# Beetech_GSM_MKR1400.net
KiCad netlist of a schematic drawn in Altium Designer
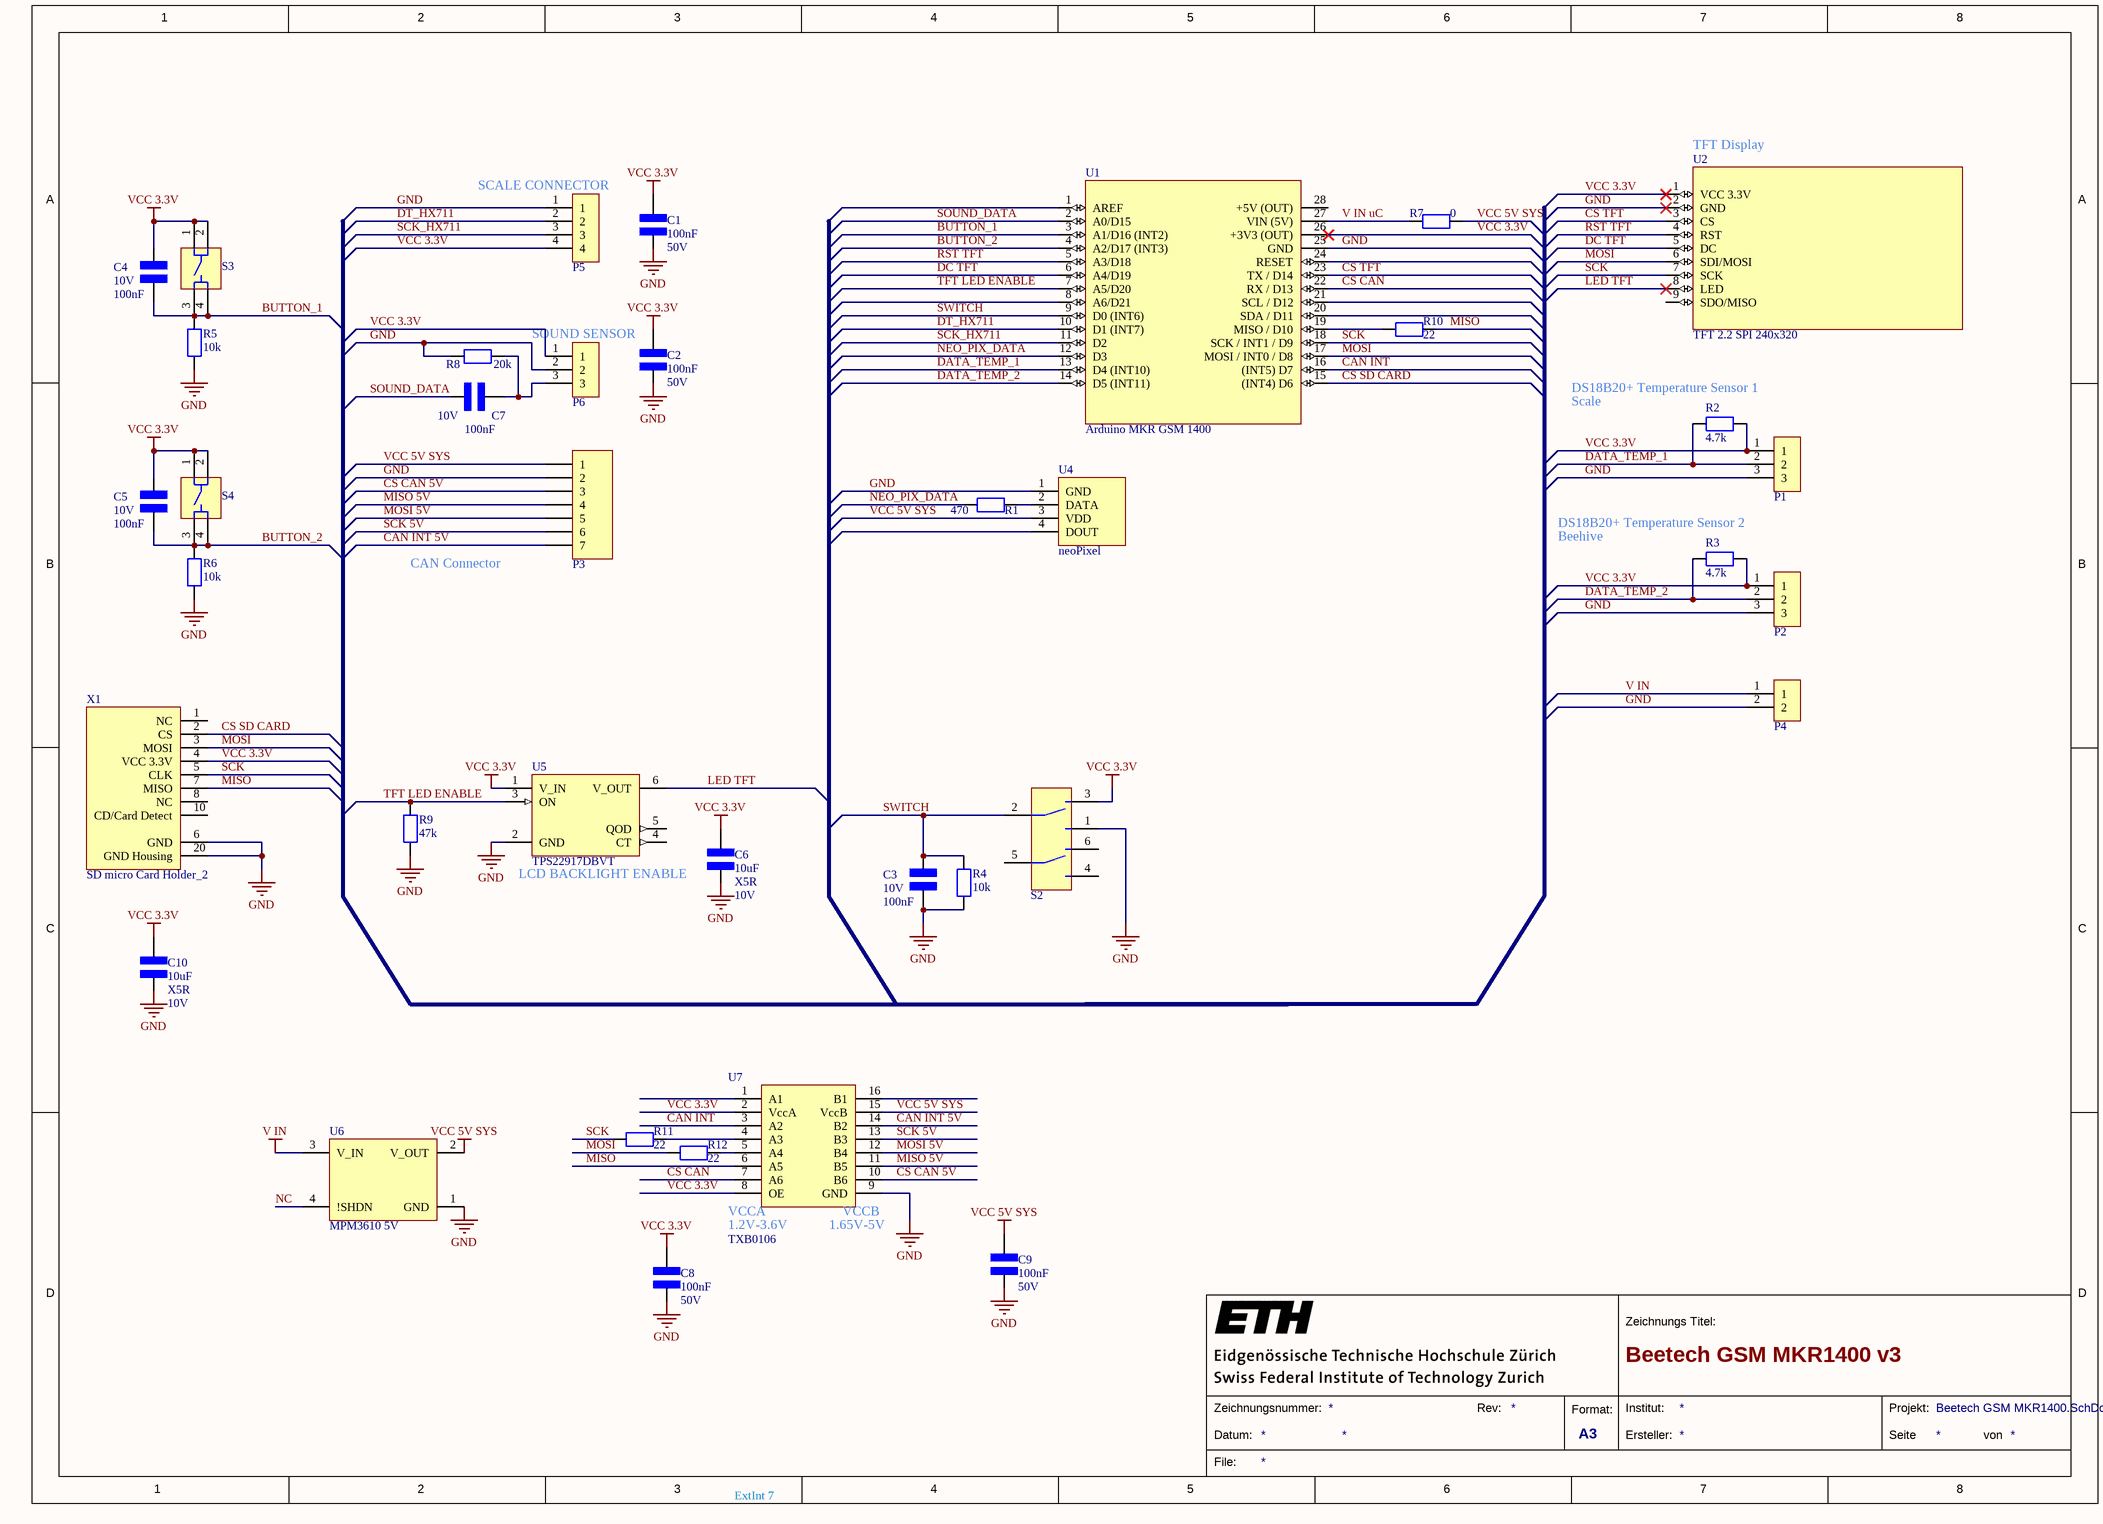
[diagram p0: Beetech GSM MKR1400.SchDoc]

(export (version "E")
  (design (tool "Eeschema 10.0.6"))
  (components
    (comp (ref "C1")
      (value "100nF")
      (footprint "CAP 0603")
      (description "C CERAMIC SMD")
      (fields (field (name "UMAX") "50V") (field (name "Comment") "100nF 0603_1"))
      (libsource (lib "Library CAP") (part "100nF 0603_1"))
    )
    (comp (ref "C2")
      (value "100nF")
      (footprint "CAP 0603")
      (description "C CERAMIC SMD")
      (fields (field (name "UMAX") "50V") (field (name "Comment") "100nF 0603_1"))
      (libsource (lib "Library CAP") (part "100nF 0603_1"))
    )
    (comp (ref "C3")
      (value "100nF")
      (footprint "CAP 0603")
      (description "C CERAMIC SMD")
      (fields (field (name "UMAX") "10V") (field (name "Comment") "100nF 0603"))
      (libsource (lib "Library CAP") (part "100nF 0603"))
    )
    (comp (ref "C4")
      (value "100nF")
      (footprint "CAP 0603")
      (description "C CERAMIC SMD")
      (fields (field (name "UMAX") "10V") (field (name "Comment") "100nF 0603"))
      (libsource (lib "Library CAP") (part "100nF 0603"))
    )
    (comp (ref "C5")
      (value "100nF")
      (footprint "CAP 0603")
      (description "C CERAMIC SMD")
      (fields (field (name "UMAX") "10V") (field (name "Comment") "100nF 0603"))
      (libsource (lib "Library CAP") (part "100nF 0603"))
    )
    (comp (ref "C6")
      (value "10uF")
      (footprint "CAP 0603")
      (description "C CERAMIC SMD")
      (fields
        (field (name "DIELEKTRIKUM") "X5R")
        (field (name "UMAX") "10V")
        (field (name "Comment") "10uF 0603")
      )
      (libsource (lib "Library CAP") (part "10uF 0603"))
    )
    (comp (ref "C7")
      (value "100nF")
      (footprint "CAP 0603")
      (description "C CERAMIC SMD")
      (fields (field (name "UMAX") "10V") (field (name "Comment") "100nF 0603"))
      (libsource (lib "") (part "100nF 0603_1"))
    )
    (comp (ref "C8")
      (value "100nF")
      (footprint "CAP 0603")
      (description "C CERAMIC SMD")
      (fields (field (name "UMAX") "50V") (field (name "Comment") "100nF 0603_1"))
      (libsource (lib "Library CAP") (part "100nF 0603_1"))
    )
    (comp (ref "C9")
      (value "100nF")
      (footprint "CAP 0603")
      (description "C CERAMIC SMD")
      (fields (field (name "UMAX") "50V") (field (name "Comment") "100nF 0603_1"))
      (libsource (lib "Library CAP") (part "100nF 0603_1"))
    )
    (comp (ref "C10")
      (value "10uF")
      (footprint "CAP 0603")
      (description "C CERAMIC SMD")
      (fields
        (field (name "DIELEKTRIKUM") "X5R")
        (field (name "UMAX") "10V")
        (field (name "Comment") "10uF 0603")
      )
      (libsource (lib "Library CAP") (part "10uF 0603"))
    )
    (comp (ref "P1")
      (value "3-Pin Right Angle Housing")
      (footprint "3PIN - RND 205-EK254-2.54-03P")
      (description "3-Pin")
      (libsource (lib "Library Scematic") (part "3-Pin Screw Terminal"))
    )
    (comp (ref "P2")
      (value "3-Pin Right Angle Housing")
      (footprint "3PIN - RND 205-EK254-2.54-03P")
      (description "3-Pin")
      (libsource (lib "Library Scematic") (part "3-Pin Screw Terminal"))
    )
    (comp (ref "P3")
      (value "8-Pin")
      (footprint "7PIN")
      (fields (field (name "PUBLISHER") "Altium Limited"))
      (libsource (lib "Library Scematic") (part "7-Pin"))
    )
    (comp (ref "P4")
      (value "2-Pin Right Angle Housing")
      (footprint "2PIN - RND 205-EK254-2.54-02P")
      (description "2-Pin")
      (libsource (lib "Library Scematic") (part "2-Pin Screw Terminal"))
    )
    (comp (ref "P5")
      (value "4-Pin Right Angle Housing")
      (footprint "4PIN - RND 205-EK254-2.54-04P")
      (description "4-Pin")
      (libsource (lib "Library Scematic") (part "4-Pin Screw Terminal"))
    )
    (comp (ref "P6")
      (value "3-Pin Right Angle Housing")
      (footprint "3PIN - RND 205-EK254-2.54-03P")
      (description "3-Pin")
      (libsource (lib "Library Scematic") (part "3-Pin Screw Terminal"))
    )
    (comp (ref "R1")
      (value "470")
      (footprint "RES 0603 FOOTPRINT")
      (description "R SMD")
      (fields (field (name "Comment") "470 Ohm 0603"))
      (libsource (lib "Library RES") (part "470 Ohm 0603"))
    )
    (comp (ref "R2")
      (value "4.7k")
      (footprint "RES 0603 FOOTPRINT")
      (description "R SMD")
      (fields (field (name "Comment") "4.7k Ohm 0603"))
      (libsource (lib "Library RES") (part "4.7k Ohm 0603"))
    )
    (comp (ref "R3")
      (value "4.7k")
      (footprint "RES 0603 FOOTPRINT")
      (description "R SMD")
      (fields (field (name "Comment") "4.7k Ohm 0603"))
      (libsource (lib "Library RES") (part "4.7k Ohm 0603"))
    )
    (comp (ref "R4")
      (value "10k")
      (footprint "RES 0603 FOOTPRINT")
      (description "R SMD")
      (fields (field (name "Comment") "10k Ohm 0603"))
      (libsource (lib "Library RES") (part "10k Ohm 0603"))
    )
    (comp (ref "R5")
      (value "10k")
      (footprint "RES 0603 FOOTPRINT")
      (description "R SMD")
      (fields (field (name "Comment") "10k Ohm 0603"))
      (libsource (lib "Library RES") (part "10k Ohm 0603"))
    )
    (comp (ref "R6")
      (value "10k")
      (footprint "RES 0603 FOOTPRINT")
      (description "R SMD")
      (fields (field (name "Comment") "10k Ohm 0603"))
      (libsource (lib "Library RES") (part "10k Ohm 0603"))
    )
    (comp (ref "R7")
      (value "0")
      (footprint "RES 0603 FOOTPRINT")
      (description "R SMD")
      (fields (field (name "Comment") "0 Ohm 0603"))
      (libsource (lib "Library RES") (part "0 Ohm 0603"))
    )
    (comp (ref "R8")
      (value "20k")
      (footprint "RES 0603 FOOTPRINT")
      (description "R SMD")
      (fields (field (name "Comment") "20k Ohm 0603"))
      (libsource (lib "Library RES") (part "20k Ohm 0603"))
    )
    (comp (ref "R9")
      (value "47k")
      (footprint "RES 0603 FOOTPRINT")
      (description "R SMD")
      (fields (field (name "Comment") "47k Ohm 0603"))
      (libsource (lib "Library RES") (part "47k Ohm 0603"))
    )
    (comp (ref "R10")
      (value "22")
      (footprint "RES 0603 FOOTPRINT")
      (description "R SMD")
      (fields (field (name "Comment") "22 Ohm 0603"))
      (libsource (lib "Library RES") (part "22 Ohm 0603"))
    )
    (comp (ref "R11")
      (value "22")
      (footprint "RES 0603 FOOTPRINT")
      (description "R SMD")
      (fields (field (name "Comment") "22 Ohm 0603"))
      (libsource (lib "Library RES") (part "22 Ohm 0603"))
    )
    (comp (ref "R12")
      (value "22")
      (footprint "RES 0603 FOOTPRINT")
      (description "R SMD")
      (fields (field (name "Comment") "22 Ohm 0603"))
      (libsource (lib "Library RES") (part "22 Ohm 0603"))
    )
    (comp (ref "S2")
      (value "Schiebeschalter EG2207")
      (footprint "Schiebeschalter on-on 2 P, EG2207")
      (description "Schiebeschalter on-on PCM12SMTR")
      (libsource (lib "Library Scematic") (part "Schiebeschalter EG2207"))
    )
    (comp (ref "S3")
      (value "Taster Print_SMD_3")
      (footprint "Taster Print - SMD - PTS647SM70SMTR2LFS")
      (description "Taster")
      (libsource (lib "Library Scematic") (part "Taster Print_SMD_6"))
    )
    (comp (ref "S4")
      (value "Taster Print_SMD_3")
      (footprint "Taster Print - SMD - PTS647SM70SMTR2LFS")
      (description "Taster")
      (libsource (lib "Library Scematic") (part "Taster Print_SMD_6"))
    )
    (comp (ref "U1")
      (value "Arduino MKR GSM 1400")
      (footprint "Arduino GSM MKR 1400 v2")
      (description "https://store.arduino.cc/arduino-mkr-gsm-1400-1415")
      (libsource (lib "Library Scematic") (part "Arduino MKR GSM 1400"))
    )
    (comp (ref "U2")
      (value "TFT 2.2 SPI 240x320")
      (footprint "TFT 2.2 SPI 240x320")
      (libsource (lib "Library Scematic") (part "TFT 2.2 SPI 240x320"))
    )
    (comp (ref "U4")
      (value "neoPixel")
      (footprint "neoPixel 5050 adafruit 1655")
      (description "neoPixel 5050 adafruit 1655")
      (libsource (lib "Library Scematic") (part "neoPixel 5050 adafruit 1655"))
    )
    (comp (ref "U5")
      (value "TPS22917DBVT")
      (footprint "SOT23 - 6")
      (description "High Side Switch")
      (libsource (lib "Library Scematic") (part "TPS22917DBVT"))
    )
    (comp (ref "U6")
      (value "MPM3610 5V")
      (footprint "MPM3610 Buck Converter")
      (description "MPM3610 5V Buck Converter Breakout - 21V In 5V Out at 1.2A")
      (libsource (lib "Library PWR") (part "MPM3610 5V Buck Converter Breakout"))
    )
    (comp (ref "U7")
      (value "TXB0106")
      (footprint "TSSOP-16L")
      (description "Level Converter TXB0106")
      (libsource (lib "Library Scematic") (part "TXB0106 Level Converter"))
    )
    (comp (ref "X1")
      (value "SD micro Card Holder_2")
      (footprint "SD Card Holder - micro - 2 - sd Card inserted")
      (description "SD micro Card  Holder")
      (libsource (lib "Library Scematic") (part "SD micro Card Holder_2"))
    )
  )
  (nets
    (net (code "1") (name "/BUTTON_1") (class "Default")
      (node (ref "C4") (pin "2") (pinfunction "2_2") (pintype "passive"))
      (node (ref "R5") (pin "2") (pinfunction "2_2") (pintype "passive"))
      (node (ref "S3") (pin "3") (pinfunction "3_3") (pintype "passive"))
      (node (ref "S3") (pin "4") (pinfunction "4_4") (pintype "passive"))
      (node (ref "U1") (pin "3") (pinfunction "A1/D16_(INT2)_3") (pintype "bidirectional"))
    )
    (net (code "2") (name "/BUTTON_2") (class "Default")
      (node (ref "C5") (pin "2") (pinfunction "2_2") (pintype "passive"))
      (node (ref "R6") (pin "2") (pinfunction "2_2") (pintype "passive"))
      (node (ref "S4") (pin "3") (pinfunction "3_3") (pintype "passive"))
      (node (ref "S4") (pin "4") (pinfunction "4_4") (pintype "passive"))
      (node (ref "U1") (pin "4") (pinfunction "A2/D17_(INT3)_4") (pintype "bidirectional"))
    )
    (net (code "3") (name "/CAN INT") (class "Default")
      (node (ref "U1") (pin "16") (pinfunction "(INT5)_D7_16") (pintype "bidirectional"))
      (node (ref "U7") (pin "3") (pinfunction "A2_3") (pintype "passive"))
    )
    (net (code "4") (name "/CAN INT 5V") (class "Default")
      (node (ref "P3") (pin "7") (pinfunction "7_7") (pintype "passive"))
      (node (ref "U7") (pin "14") (pinfunction "B2_14") (pintype "passive"))
    )
    (net (code "5") (name "/CS CAN") (class "Default")
      (node (ref "U1") (pin "22") (pinfunction "RX_/_D13_22") (pintype "bidirectional"))
      (node (ref "U7") (pin "7") (pinfunction "A6_7") (pintype "passive"))
    )
    (net (code "6") (name "/CS CAN 5V") (class "Default")
      (node (ref "P3") (pin "3") (pinfunction "3_3") (pintype "passive"))
      (node (ref "U7") (pin "10") (pinfunction "B6_10") (pintype "passive"))
    )
    (net (code "7") (name "/CS SD CARD") (class "Default")
      (node (ref "U1") (pin "15") (pinfunction "(INT4)_D6_15") (pintype "bidirectional"))
      (node (ref "X1") (pin "2") (pinfunction "CS_2") (pintype "passive"))
    )
    (net (code "8") (name "/CS TFT") (class "Default")
      (node (ref "U1") (pin "23") (pinfunction "TX_/_D14_23") (pintype "bidirectional"))
      (node (ref "U2") (pin "3") (pinfunction "CS_3") (pintype "bidirectional"))
    )
    (net (code "9") (name "/DATA_TEMP_1") (class "Default")
      (node (ref "P1") (pin "2") (pinfunction "2_2") (pintype "passive"))
      (node (ref "R2") (pin "2") (pinfunction "2_2") (pintype "passive"))
      (node (ref "U1") (pin "13") (pinfunction "D4_(INT10)_13") (pintype "bidirectional"))
    )
    (net (code "10") (name "/DATA_TEMP_2") (class "Default")
      (node (ref "P2") (pin "2") (pinfunction "2_2") (pintype "passive"))
      (node (ref "R3") (pin "2") (pinfunction "2_2") (pintype "passive"))
      (node (ref "U1") (pin "14") (pinfunction "D5_(INT11)_14") (pintype "bidirectional"))
    )
    (net (code "11") (name "/DC TFT") (class "Default")
      (node (ref "U1") (pin "6") (pinfunction "A4/D19_6") (pintype "bidirectional"))
      (node (ref "U2") (pin "5") (pinfunction "DC_5") (pintype "bidirectional"))
    )
    (net (code "12") (name "/DT_HX711") (class "Default")
      (node (ref "P5") (pin "2") (pinfunction "2_2") (pintype "passive"))
      (node (ref "U1") (pin "10") (pinfunction "D1_(INT7)_10") (pintype "bidirectional"))
    )
    (net (code "13") (name "/LED TFT") (class "Default")
      (node (ref "U2") (pin "8") (pinfunction "LED_8") (pintype "bidirectional"))
      (node (ref "U5") (pin "6") (pinfunction "V_OUT_6") (pintype "power_in"))
    )
    (net (code "14") (name "/MISO") (class "Default")
      (node (ref "R10") (pin "2") (pinfunction "2_2") (pintype "passive"))
      (node (ref "U7") (pin "6") (pinfunction "A5_6") (pintype "passive"))
      (node (ref "X1") (pin "7") (pinfunction "MISO_7") (pintype "passive"))
    )
    (net (code "15") (name "/MISO 5V") (class "Default")
      (node (ref "P3") (pin "4") (pinfunction "4_4") (pintype "passive"))
      (node (ref "U7") (pin "11") (pinfunction "B5_11") (pintype "passive"))
    )
    (net (code "16") (name "/MOSI") (class "Default")
      (node (ref "R12") (pin "1") (pinfunction "1_1") (pintype "passive"))
      (node (ref "U1") (pin "17") (pinfunction "MOSI_/_INT0_/_D8_17") (pintype "bidirectional"))
      (node (ref "U2") (pin "6") (pinfunction "SDI/MOSI_6") (pintype "bidirectional"))
      (node (ref "X1") (pin "3") (pinfunction "MOSI_3") (pintype "passive"))
    )
    (net (code "17") (name "/MOSI 5V") (class "Default")
      (node (ref "P3") (pin "5") (pinfunction "5_5") (pintype "passive"))
      (node (ref "U7") (pin "12") (pinfunction "B4_12") (pintype "passive"))
    )
    (net (code "18") (name "/NC") (class "Default")
      (node (ref "U6") (pin "4") (pinfunction "!SHDN_4") (pintype "power_in"))
    )
    (net (code "19") (name "/NEO_PIX_DATA") (class "Default")
      (node (ref "R1") (pin "1") (pinfunction "1_1") (pintype "passive"))
      (node (ref "U1") (pin "12") (pinfunction "D3_12") (pintype "bidirectional"))
    )
    (net (code "20") (name "/RST TFT") (class "Default")
      (node (ref "U1") (pin "5") (pinfunction "A3/D18_5") (pintype "bidirectional"))
      (node (ref "U2") (pin "4") (pinfunction "RST_4") (pintype "bidirectional"))
    )
    (net (code "21") (name "/SCK") (class "Default")
      (node (ref "R11") (pin "1") (pinfunction "1_1") (pintype "passive"))
      (node (ref "U1") (pin "18") (pinfunction "SCK_/_INT1_/_D9_18") (pintype "bidirectional"))
      (node (ref "U2") (pin "7") (pinfunction "SCK_7") (pintype "bidirectional"))
      (node (ref "X1") (pin "5") (pinfunction "CLK_5") (pintype "passive"))
    )
    (net (code "22") (name "/SCK 5V") (class "Default")
      (node (ref "P3") (pin "6") (pinfunction "6_6") (pintype "passive"))
      (node (ref "U7") (pin "13") (pinfunction "B3_13") (pintype "passive"))
    )
    (net (code "23") (name "/SCK_HX711") (class "Default")
      (node (ref "P5") (pin "3") (pinfunction "3_3") (pintype "passive"))
      (node (ref "U1") (pin "11") (pinfunction "D2_11") (pintype "bidirectional"))
    )
    (net (code "24") (name "/SOUND_DATA") (class "Default")
      (node (ref "C7") (pin "1") (pinfunction "1_1") (pintype "passive"))
      (node (ref "U1") (pin "2") (pinfunction "A0/D15_2") (pintype "bidirectional"))
    )
    (net (code "25") (name "/SWITCH") (class "Default")
      (node (ref "C3") (pin "1") (pinfunction "1_1") (pintype "passive"))
      (node (ref "R4") (pin "2") (pinfunction "2_2") (pintype "passive"))
      (node (ref "S2") (pin "2") (pinfunction "2_2") (pintype "passive"))
      (node (ref "U1") (pin "9") (pinfunction "D0_(INT6)_9") (pintype "bidirectional"))
    )
    (net (code "26") (name "/TFT LED ENABLE") (class "Default")
      (node (ref "R9") (pin "2") (pinfunction "2_2") (pintype "passive"))
      (node (ref "U1") (pin "7") (pinfunction "A5/D20_7") (pintype "bidirectional"))
      (node (ref "U5") (pin "3") (pinfunction "ON_3") (pintype "input"))
    )
    (net (code "27") (name "/V IN uC") (class "Default")
      (node (ref "R7") (pin "1") (pinfunction "1_1") (pintype "passive"))
      (node (ref "U1") (pin "27") (pinfunction "VIN_(5V)_27") (pintype "power_in"))
    )
    (net (code "28") (name "GND") (class "Default")
      (node (ref "C1") (pin "1") (pinfunction "1_1") (pintype "passive"))
      (node (ref "C10") (pin "1") (pinfunction "1_1") (pintype "passive"))
      (node (ref "C2") (pin "1") (pinfunction "1_1") (pintype "passive"))
      (node (ref "C3") (pin "2") (pinfunction "2_2") (pintype "passive"))
      (node (ref "C6") (pin "1") (pinfunction "1_1") (pintype "passive"))
      (node (ref "C8") (pin "1") (pinfunction "1_1") (pintype "passive"))
      (node (ref "C9") (pin "1") (pinfunction "1_1") (pintype "passive"))
      (node (ref "P1") (pin "3") (pinfunction "3_3") (pintype "passive"))
      (node (ref "P2") (pin "3") (pinfunction "3_3") (pintype "passive"))
      (node (ref "P3") (pin "2") (pinfunction "2_2") (pintype "passive"))
      (node (ref "P4") (pin "2") (pinfunction "2_2") (pintype "passive"))
      (node (ref "P5") (pin "1") (pinfunction "1_1") (pintype "passive"))
      (node (ref "P6") (pin "2") (pinfunction "2_2") (pintype "passive"))
      (node (ref "R4") (pin "1") (pinfunction "1_1") (pintype "passive"))
      (node (ref "R5") (pin "1") (pinfunction "1_1") (pintype "passive"))
      (node (ref "R6") (pin "1") (pinfunction "1_1") (pintype "passive"))
      (node (ref "R8") (pin "1") (pinfunction "1_1") (pintype "passive"))
      (node (ref "R9") (pin "1") (pinfunction "1_1") (pintype "passive"))
      (node (ref "S2") (pin "1") (pinfunction "1_1") (pintype "passive"))
      (node (ref "U1") (pin "25") (pinfunction "GND_25") (pintype "power_in"))
      (node (ref "U2") (pin "2") (pinfunction "GND_2") (pintype "bidirectional"))
      (node (ref "U4") (pin "1") (pinfunction "GND_1") (pintype "passive"))
      (node (ref "U5") (pin "2") (pinfunction "GND_2") (pintype "power_in"))
      (node (ref "U6") (pin "1") (pinfunction "GND_1") (pintype "power_in"))
      (node (ref "U7") (pin "9") (pinfunction "GND_9") (pintype "passive"))
      (node (ref "X1") (pin "20") (pinfunction "GND_Housing_20") (pintype "passive"))
      (node (ref "X1") (pin "6") (pinfunction "GND_6") (pintype "passive"))
    )
    (net (code "29") (name "Net-(C7-Pad2)") (class "Default")
      (node (ref "C7") (pin "2") (pinfunction "2_2") (pintype "passive"))
      (node (ref "P6") (pin "3") (pinfunction "3_3") (pintype "passive"))
      (node (ref "R8") (pin "2") (pinfunction "2_2") (pintype "passive"))
    )
    (net (code "30") (name "Net-(U1-MISO_{slash}_D10)") (class "Default")
      (node (ref "R10") (pin "1") (pinfunction "1_1") (pintype "passive"))
      (node (ref "U1") (pin "19") (pinfunction "MISO_/_D10_19") (pintype "bidirectional"))
    )
    (net (code "31") (name "Net-(U4-DATA)") (class "Default")
      (node (ref "R1") (pin "2") (pinfunction "2_2") (pintype "passive"))
      (node (ref "U4") (pin "2") (pinfunction "DATA_2") (pintype "passive"))
    )
    (net (code "32") (name "Net-(U7-A3)") (class "Default")
      (node (ref "R11") (pin "2") (pinfunction "2_2") (pintype "passive"))
      (node (ref "U7") (pin "4") (pinfunction "A3_4") (pintype "passive"))
    )
    (net (code "33") (name "Net-(U7-A4)") (class "Default")
      (node (ref "R12") (pin "2") (pinfunction "2_2") (pintype "passive"))
      (node (ref "U7") (pin "5") (pinfunction "A4_5") (pintype "passive"))
    )
    (net (code "34") (name "V IN") (class "Default")
      (node (ref "P4") (pin "1") (pinfunction "1_1") (pintype "passive"))
      (node (ref "U6") (pin "3") (pinfunction "V_IN_3") (pintype "power_in"))
    )
    (net (code "35") (name "VCC 3.3V") (class "Default")
      (node (ref "C1") (pin "2") (pinfunction "2_2") (pintype "passive"))
      (node (ref "C10") (pin "2") (pinfunction "2_2") (pintype "passive"))
      (node (ref "C2") (pin "2") (pinfunction "2_2") (pintype "passive"))
      (node (ref "C4") (pin "1") (pinfunction "1_1") (pintype "passive"))
      (node (ref "C5") (pin "1") (pinfunction "1_1") (pintype "passive"))
      (node (ref "C6") (pin "2") (pinfunction "2_2") (pintype "passive"))
      (node (ref "C8") (pin "2") (pinfunction "2_2") (pintype "passive"))
      (node (ref "P1") (pin "1") (pinfunction "1_1") (pintype "passive"))
      (node (ref "P2") (pin "1") (pinfunction "1_1") (pintype "passive"))
      (node (ref "P5") (pin "4") (pinfunction "4_4") (pintype "passive"))
      (node (ref "P6") (pin "1") (pinfunction "1_1") (pintype "passive"))
      (node (ref "R2") (pin "1") (pinfunction "1_1") (pintype "passive"))
      (node (ref "R3") (pin "1") (pinfunction "1_1") (pintype "passive"))
      (node (ref "S2") (pin "3") (pinfunction "3_3") (pintype "passive"))
      (node (ref "S3") (pin "1") (pinfunction "1_1") (pintype "passive"))
      (node (ref "S3") (pin "2") (pinfunction "2_2") (pintype "passive"))
      (node (ref "S4") (pin "1") (pinfunction "1_1") (pintype "passive"))
      (node (ref "S4") (pin "2") (pinfunction "2_2") (pintype "passive"))
      (node (ref "U1") (pin "26") (pinfunction "+3V3_(OUT)_26") (pintype "power_in"))
      (node (ref "U2") (pin "1") (pinfunction "VCC_3.3V_1") (pintype "bidirectional"))
      (node (ref "U5") (pin "1") (pinfunction "V_IN_1") (pintype "power_in"))
      (node (ref "U7") (pin "2") (pinfunction "VccA_2") (pintype "passive"))
      (node (ref "U7") (pin "8") (pinfunction "OE_8") (pintype "passive"))
      (node (ref "X1") (pin "4") (pinfunction "VCC_3.3V_4") (pintype "passive"))
    )
    (net (code "36") (name "VCC 5V SYS") (class "Default")
      (node (ref "C9") (pin "2") (pinfunction "2_2") (pintype "passive"))
      (node (ref "P3") (pin "1") (pinfunction "1_1") (pintype "passive"))
      (node (ref "R7") (pin "2") (pinfunction "2_2") (pintype "passive"))
      (node (ref "U4") (pin "3") (pinfunction "VDD_3") (pintype "passive"))
      (node (ref "U6") (pin "2") (pinfunction "V_OUT_2") (pintype "power_in"))
      (node (ref "U7") (pin "15") (pinfunction "VccB_15") (pintype "passive"))
    )
    (net (code "37") (name "unconnected-(S2-Pad4)") (class "Default")
      (node (ref "S2") (pin "4") (pinfunction "4_4") (pintype "passive"))
    )
    (net (code "38") (name "unconnected-(S2-Pad5)") (class "Default")
      (node (ref "S2") (pin "5") (pinfunction "5_5") (pintype "passive"))
    )
    (net (code "39") (name "unconnected-(S2-Pad6)") (class "Default")
      (node (ref "S2") (pin "6") (pinfunction "6_6") (pintype "passive"))
    )
    (net (code "40") (name "unconnected-(U1-+5V_(OUT)-Pad28)") (class "Default")
      (node (ref "U1") (pin "28") (pinfunction "+5V_(OUT)_28") (pintype "power_in"))
    )
    (net (code "41") (name "unconnected-(U1-A6{slash}D21-Pad8)") (class "Default")
      (node (ref "U1") (pin "8") (pinfunction "A6/D21_8") (pintype "bidirectional"))
    )
    (net (code "42") (name "unconnected-(U1-AREF-Pad1)") (class "Default")
      (node (ref "U1") (pin "1") (pinfunction "AREF_1") (pintype "bidirectional"))
    )
    (net (code "43") (name "unconnected-(U1-RESET-Pad24)") (class "Default")
      (node (ref "U1") (pin "24") (pinfunction "RESET_24") (pintype "bidirectional"))
    )
    (net (code "44") (name "unconnected-(U1-SCL_{slash}_D12-Pad21)") (class "Default")
      (node (ref "U1") (pin "21") (pinfunction "SCL_/_D12_21") (pintype "bidirectional"))
    )
    (net (code "45") (name "unconnected-(U1-SDA_{slash}_D11-Pad20)") (class "Default")
      (node (ref "U1") (pin "20") (pinfunction "SDA_/_D11_20") (pintype "bidirectional"))
    )
    (net (code "46") (name "unconnected-(U2-SDO{slash}MISO-Pad9)") (class "Default")
      (node (ref "U2") (pin "9") (pinfunction "SDO/MISO_9") (pintype "bidirectional"))
    )
    (net (code "47") (name "unconnected-(U4-DOUT-Pad4)") (class "Default")
      (node (ref "U4") (pin "4") (pinfunction "DOUT_4") (pintype "passive"))
    )
    (net (code "48") (name "unconnected-(U5-CT-Pad4)") (class "Default")
      (node (ref "U5") (pin "4") (pinfunction "CT_4") (pintype "output"))
    )
    (net (code "49") (name "unconnected-(U5-QOD-Pad5)") (class "Default")
      (node (ref "U5") (pin "5") (pinfunction "QOD_5") (pintype "output"))
    )
    (net (code "50") (name "unconnected-(U7-A1-Pad1)") (class "Default")
      (node (ref "U7") (pin "1") (pinfunction "A1_1") (pintype "power_in"))
    )
    (net (code "51") (name "unconnected-(U7-B1-Pad16)") (class "Default")
      (node (ref "U7") (pin "16") (pinfunction "B1_16") (pintype "passive"))
    )
    (net (code "52") (name "unconnected-(X1-CD{slash}Card_Detect-Pad10)") (class "Default")
      (node (ref "X1") (pin "10") (pinfunction "CD/Card_Detect_10") (pintype "passive"))
    )
    (net (code "53") (name "unconnected-(X1-NC-Pad1)") (class "Default")
      (node (ref "X1") (pin "1") (pinfunction "NC_1") (pintype "passive"))
    )
    (net (code "54") (name "unconnected-(X1-NC-Pad8)") (class "Default")
      (node (ref "X1") (pin "8") (pinfunction "NC_8") (pintype "passive"))
    )
  )
)
